# Logics_I2C_SMD_Adapter_v1_4.net
KiCad netlist of a schematic drawn in EAGLE
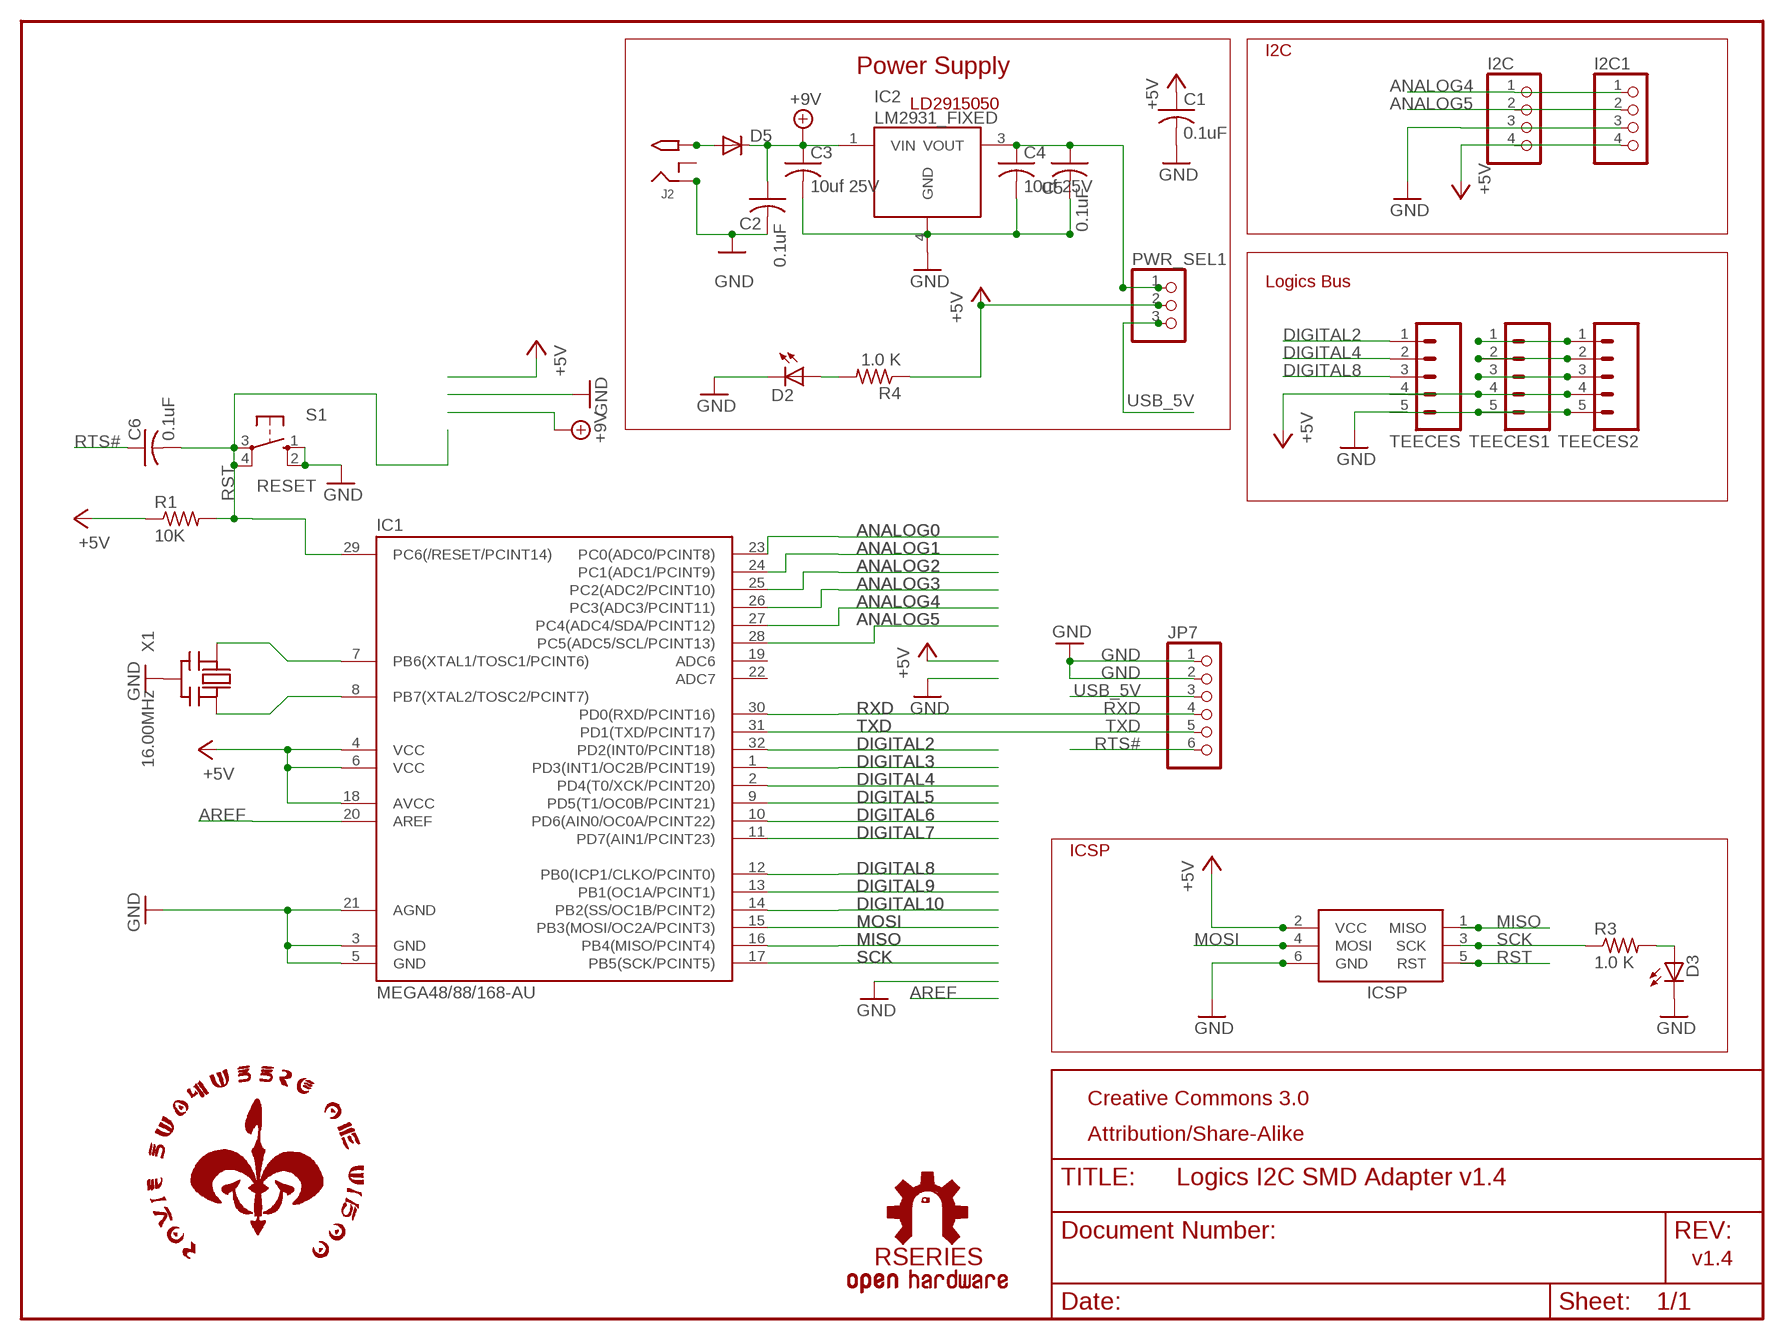
[diagram p0: schematic, sheet 1]

(export (version "E")
  (design (tool "Eeschema 10.0.6"))
  (components
    (comp (ref "C1")
      (value "0.1uF")
      (footprint "eagle-import:C1206K")
      (libsource (lib "eagle-import") (part "C-USC1206K"))
    )
    (comp (ref "C2")
      (value "0.1uF")
      (footprint "eagle-import:C1206K")
      (libsource (lib "eagle-import") (part "C-USC1206K"))
    )
    (comp (ref "C3")
      (value "10uf 25V")
      (footprint "eagle-import:C1206K")
      (libsource (lib "eagle-import") (part "rcl_C-USC1206K"))
    )
    (comp (ref "C4")
      (value "10uf 25V")
      (footprint "eagle-import:C1206K")
      (libsource (lib "eagle-import") (part "rcl_C-USC1206K"))
    )
    (comp (ref "C5")
      (value "0.1uF")
      (footprint "eagle-import:C1206K")
      (libsource (lib "eagle-import") (part "C-USC1206K"))
    )
    (comp (ref "C6")
      (value "0.1uF")
      (footprint "eagle-import:C1206K")
      (libsource (lib "eagle-import") (part "C-USC1206K"))
    )
    (comp (ref "D2")
      (value "LEDCHIPLED_1206")
      (footprint "eagle-import:CHIPLED_1206")
      (libsource (lib "eagle-import") (part "LEDCHIPLED_1206"))
    )
    (comp (ref "D3")
      (value "Green")
      (footprint "eagle-import:CHIPLED_1206")
      (libsource (lib "eagle-import") (part "LEDCHIPLED_1206"))
    )
    (comp (ref "D5")
      (value "DIODE-SMB")
      (footprint "eagle-import:SMB")
      (libsource (lib "eagle-import") (part "DIODE-SMB"))
    )
    (comp (ref "I2C")
      (value "PINHD-1X4CB")
      (footprint "eagle-import:1X04-CB")
      (libsource (lib "eagle-import") (part "PINHD-1X4CB"))
    )
    (comp (ref "I2C1")
      (value "PINHD-1X4CB")
      (footprint "eagle-import:1X04-CB")
      (libsource (lib "eagle-import") (part "PINHD-1X4CB"))
    )
    (comp (ref "IC1")
      (value "MEGA48/88/168-AU")
      (footprint "eagle-import:TQFP32-08")
      (libsource (lib "eagle-import") (part "MEGA48/88/168-AU"))
    )
    (comp (ref "IC2")
      (value "LM2931_FIXED")
      (footprint "eagle-import:DPAK")
      (libsource (lib "eagle-import") (part "LM2931_FIXED"))
    )
    (comp (ref "ICSP")
      (value "AVRISP-6")
      (footprint "eagle-import:AVRISP")
      (libsource (lib "eagle-import") (part "AVRISP-6"))
    )
    (comp (ref "J2")
      (value "2.1MMJACK")
      (footprint "eagle-import:PJ-102A")
      (libsource (lib "eagle-import") (part "2.1MMJACK"))
    )
    (comp (ref "JP7")
      (value "PINHD-1X6CLEAN")
      (footprint "eagle-import:1X06-CLEAN")
      (libsource (lib "eagle-import") (part "PINHD-1X6CLEAN"))
    )
    (comp (ref "PWR_SEL1")
      (value "PINHD-1X3")
      (footprint "eagle-import:1X03")
      (libsource (lib "eagle-import") (part "PINHD-1X3"))
    )
    (comp (ref "R1")
      (value "10K")
      (footprint "eagle-import:R1206")
      (libsource (lib "eagle-import") (part "rcl-ez_R-US_R1206"))
    )
    (comp (ref "R3")
      (value "1.0 K")
      (footprint "eagle-import:M1206")
      (libsource (lib "eagle-import") (part "R-US_M1206"))
    )
    (comp (ref "R4")
      (value "1.0 K")
      (footprint "eagle-import:M1206")
      (libsource (lib "eagle-import") (part "R-US_M1206"))
    )
    (comp (ref "S1")
      (value "RESET")
      (footprint "eagle-import:B3F-10XX")
      (libsource (lib "eagle-import") (part "10-XX"))
    )
    (comp (ref "TEECES")
      (value "M05PTH")
      (footprint "eagle-import:1X05")
      (libsource (lib "eagle-import") (part "M05PTH"))
    )
    (comp (ref "TEECES1")
      (value "M05PTH")
      (footprint "eagle-import:1X05")
      (libsource (lib "eagle-import") (part "M05PTH"))
    )
    (comp (ref "TEECES2")
      (value "M05PTH")
      (footprint "eagle-import:1X05")
      (libsource (lib "eagle-import") (part "M05PTH"))
    )
    (comp (ref "U$1")
      (value "ROYAL-ENGINEERS-OF-NABOOSMALL")
      (footprint "eagle-import:ROYAL-ENGINEERS-OF-NABOO-SMALL")
      (libsource (lib "eagle-import") (part "ROYAL-ENGINEERS-OF-NABOOSMALL"))
    )
    (comp (ref "U$2")
      (value "RSERIES-OSHW-LOGOMEDIUM")
      (footprint "eagle-import:RSERIES-OSHW-LOGO-MEDIUM")
      (libsource (lib "eagle-import") (part "RSERIES-OSHW-LOGOMEDIUM"))
    )
    (comp (ref "X1")
      (value "16.00MHz")
      (footprint "eagle-import:CERM_OSC")
      (libsource (lib "eagle-import") (part "CERMOSCILL"))
    )
  )
  (nets
    (net (code "1") (name "+5V") (class "Default")
      (node (ref "C1") (pin "1") (pinfunction "1_1") (pintype "passive"))
      (node (ref "I2C") (pin "4") (pinfunction "4_4") (pintype "passive"))
      (node (ref "I2C1") (pin "4") (pinfunction "4_4") (pintype "passive"))
      (node (ref "IC1") (pin "18") (pinfunction "AVCC_18") (pintype "passive"))
      (node (ref "IC1") (pin "4") (pinfunction "VCC_4") (pintype "power_in"))
      (node (ref "IC1") (pin "6") (pinfunction "VCC_6") (pintype "power_in"))
      (node (ref "ICSP") (pin "2") (pinfunction "VCC_2") (pintype "power_in"))
      (node (ref "PWR_SEL1") (pin "2") (pinfunction "2_2") (pintype "passive"))
      (node (ref "R1") (pin "1") (pinfunction "1_1") (pintype "passive"))
      (node (ref "R4") (pin "1") (pinfunction "1_1") (pintype "passive"))
      (node (ref "TEECES") (pin "4") (pinfunction "4_4") (pintype "passive"))
      (node (ref "TEECES1") (pin "4") (pinfunction "4_4") (pintype "passive"))
      (node (ref "TEECES2") (pin "4") (pinfunction "4_4") (pintype "passive"))
    )
    (net (code "2") (name "+9V") (class "Default")
      (node (ref "C2") (pin "1") (pinfunction "1_1") (pintype "passive"))
      (node (ref "C3") (pin "1") (pinfunction "1_1") (pintype "passive"))
      (node (ref "D5") (pin "C") (pinfunction "C_C") (pintype "passive"))
      (node (ref "IC2") (pin "1") (pinfunction "VIN_1") (pintype "bidirectional"))
    )
    (net (code "3") (name "/ANALOG0") (class "Default")
      (node (ref "IC1") (pin "23") (pinfunction "PC0(ADC0/PCINT8)_23") (pintype "bidirectional"))
    )
    (net (code "4") (name "/ANALOG1") (class "Default")
      (node (ref "IC1") (pin "24") (pinfunction "PC1(ADC1/PCINT9)_24") (pintype "bidirectional"))
    )
    (net (code "5") (name "/ANALOG2") (class "Default")
      (node (ref "IC1") (pin "25") (pinfunction "PC2(ADC2/PCINT10)_25") (pintype "bidirectional"))
    )
    (net (code "6") (name "/ANALOG3") (class "Default")
      (node (ref "IC1") (pin "26") (pinfunction "PC3(ADC3/PCINT11)_26") (pintype "bidirectional"))
    )
    (net (code "7") (name "/ANALOG4") (class "Default")
      (node (ref "I2C") (pin "1") (pinfunction "1_1") (pintype "passive"))
      (node (ref "I2C1") (pin "1") (pinfunction "1_1") (pintype "passive"))
      (node (ref "IC1") (pin "27") (pinfunction "PC4(ADC4/SDA/PCINT12)_27") (pintype "bidirectional"))
    )
    (net (code "8") (name "/ANALOG5") (class "Default")
      (node (ref "I2C") (pin "2") (pinfunction "2_2") (pintype "passive"))
      (node (ref "I2C1") (pin "2") (pinfunction "2_2") (pintype "passive"))
      (node (ref "IC1") (pin "28") (pinfunction "PC5(ADC5/SCL/PCINT13)_28") (pintype "bidirectional"))
    )
    (net (code "9") (name "/AREF") (class "Default")
      (node (ref "IC1") (pin "20") (pinfunction "AREF_20") (pintype "passive"))
    )
    (net (code "10") (name "/DIGITAL2") (class "Default")
      (node (ref "IC1") (pin "32") (pinfunction "PD2(INT0/PCINT18)_32") (pintype "bidirectional"))
      (node (ref "TEECES") (pin "1") (pinfunction "1_1") (pintype "passive"))
    )
    (net (code "11") (name "/DIGITAL3") (class "Default")
      (node (ref "IC1") (pin "1") (pinfunction "PD3(INT1/OC2B/PCINT19)_1") (pintype "bidirectional"))
    )
    (net (code "12") (name "/DIGITAL4") (class "Default")
      (node (ref "IC1") (pin "2") (pinfunction "PD4(T0/XCK/PCINT20)_2") (pintype "bidirectional"))
      (node (ref "TEECES") (pin "2") (pinfunction "2_2") (pintype "passive"))
    )
    (net (code "13") (name "/DIGITAL5") (class "Default")
      (node (ref "IC1") (pin "9") (pinfunction "PD5(T1/OC0B/PCINT21)_9") (pintype "bidirectional"))
    )
    (net (code "14") (name "/DIGITAL6") (class "Default")
      (node (ref "IC1") (pin "10") (pinfunction "PD6(AIN0/OC0A/PCINT22)_10") (pintype "bidirectional"))
    )
    (net (code "15") (name "/DIGITAL7") (class "Default")
      (node (ref "IC1") (pin "11") (pinfunction "PD7(AIN1/PCINT23)_11") (pintype "bidirectional"))
    )
    (net (code "16") (name "/DIGITAL8") (class "Default")
      (node (ref "IC1") (pin "12") (pinfunction "PB0(ICP1/CLKO/PCINT0)_12") (pintype "bidirectional"))
      (node (ref "TEECES") (pin "3") (pinfunction "3_3") (pintype "passive"))
    )
    (net (code "17") (name "/DIGITAL9") (class "Default")
      (node (ref "IC1") (pin "13") (pinfunction "PB1(OC1A/PCINT1)_13") (pintype "bidirectional"))
    )
    (net (code "18") (name "/DIGITAL10") (class "Default")
      (node (ref "IC1") (pin "14") (pinfunction "PB2(SS/OC1B/PCINT2)_14") (pintype "bidirectional"))
    )
    (net (code "19") (name "/MISO") (class "Default")
      (node (ref "IC1") (pin "16") (pinfunction "PB4(MISO/PCINT4)_16") (pintype "bidirectional"))
      (node (ref "ICSP") (pin "1") (pinfunction "MISO_1") (pintype "input"))
    )
    (net (code "20") (name "/MOSI") (class "Default")
      (node (ref "IC1") (pin "15") (pinfunction "PB3(MOSI/OC2A/PCINT3)_15") (pintype "bidirectional"))
      (node (ref "ICSP") (pin "4") (pinfunction "MOSI_4") (pintype "output"))
    )
    (net (code "21") (name "/RST") (class "Default")
      (node (ref "C6") (pin "2") (pinfunction "2_2") (pintype "passive"))
      (node (ref "IC1") (pin "29") (pinfunction "PC6(/RESET/PCINT14)_29") (pintype "bidirectional"))
      (node (ref "ICSP") (pin "5") (pinfunction "RST_5") (pintype "output"))
      (node (ref "R1") (pin "2") (pinfunction "2_2") (pintype "passive"))
      (node (ref "S1") (pin "3") (pinfunction "P_3") (pintype "passive"))
      (node (ref "S1") (pin "4") (pinfunction "P1_4") (pintype "passive"))
    )
    (net (code "22") (name "/RTS#") (class "Default")
      (node (ref "C6") (pin "1") (pinfunction "1_1") (pintype "passive"))
      (node (ref "JP7") (pin "6") (pinfunction "6_6") (pintype "passive"))
    )
    (net (code "23") (name "/RXD") (class "Default")
      (node (ref "IC1") (pin "30") (pinfunction "PD0(RXD/PCINT16)_30") (pintype "bidirectional"))
      (node (ref "JP7") (pin "4") (pinfunction "4_4") (pintype "passive"))
    )
    (net (code "24") (name "/SCK") (class "Default")
      (node (ref "IC1") (pin "17") (pinfunction "PB5(SCK/PCINT5)_17") (pintype "bidirectional"))
      (node (ref "ICSP") (pin "3") (pinfunction "SCK_3") (pintype "output"))
      (node (ref "R3") (pin "1") (pinfunction "1_1") (pintype "passive"))
    )
    (net (code "25") (name "/TXD") (class "Default")
      (node (ref "IC1") (pin "31") (pinfunction "PD1(TXD/PCINT17)_31") (pintype "bidirectional"))
      (node (ref "JP7") (pin "5") (pinfunction "5_5") (pintype "passive"))
    )
    (net (code "26") (name "/USB_5V") (class "Default")
      (node (ref "JP7") (pin "3") (pinfunction "3_3") (pintype "passive"))
      (node (ref "PWR_SEL1") (pin "3") (pinfunction "3_3") (pintype "passive"))
    )
    (net (code "27") (name "GND") (class "Default")
      (node (ref "C1") (pin "2") (pinfunction "2_2") (pintype "passive"))
      (node (ref "C2") (pin "2") (pinfunction "2_2") (pintype "passive"))
      (node (ref "D2") (pin "C") (pinfunction "C_C") (pintype "passive"))
      (node (ref "D3") (pin "C") (pinfunction "C_C") (pintype "passive"))
      (node (ref "I2C") (pin "3") (pinfunction "3_3") (pintype "passive"))
      (node (ref "I2C1") (pin "3") (pinfunction "3_3") (pintype "passive"))
      (node (ref "IC1") (pin "21") (pinfunction "AGND_21") (pintype "power_in"))
      (node (ref "IC1") (pin "3") (pinfunction "GND_3") (pintype "power_in"))
      (node (ref "IC1") (pin "5") (pinfunction "GND_5") (pintype "power_in"))
      (node (ref "IC2") (pin "4") (pinfunction "GND_4") (pintype "bidirectional"))
      (node (ref "ICSP") (pin "6") (pinfunction "GND_6") (pintype "power_in"))
      (node (ref "J2") (pin "RING") (pinfunction "RING_RING") (pintype "bidirectional"))
      (node (ref "JP7") (pin "1") (pinfunction "1_1") (pintype "passive"))
      (node (ref "JP7") (pin "2") (pinfunction "2_2") (pintype "passive"))
      (node (ref "S1") (pin "1") (pinfunction "S_1") (pintype "passive"))
      (node (ref "S1") (pin "2") (pinfunction "S1_2") (pintype "passive"))
      (node (ref "TEECES") (pin "5") (pinfunction "5_5") (pintype "passive"))
      (node (ref "TEECES1") (pin "5") (pinfunction "5_5") (pintype "passive"))
      (node (ref "TEECES2") (pin "5") (pinfunction "5_5") (pintype "passive"))
      (node (ref "X1") (pin "P$2") (pinfunction "GND_P$2") (pintype "bidirectional"))
    )
    (net (code "28") (name "Net-(C3-Pad2)") (class "Default")
      (node (ref "C3") (pin "2") (pinfunction "2_2") (pintype "passive"))
      (node (ref "C4") (pin "2") (pinfunction "2_2") (pintype "passive"))
      (node (ref "C5") (pin "2") (pinfunction "2_2") (pintype "passive"))
    )
    (net (code "29") (name "Net-(D2-PadA)") (class "Default")
      (node (ref "D2") (pin "A") (pinfunction "A_A") (pintype "passive"))
      (node (ref "R4") (pin "2") (pinfunction "2_2") (pintype "passive"))
    )
    (net (code "30") (name "Net-(D3-PadA)") (class "Default")
      (node (ref "D3") (pin "A") (pinfunction "A_A") (pintype "passive"))
      (node (ref "R3") (pin "2") (pinfunction "2_2") (pintype "passive"))
    )
    (net (code "31") (name "Net-(D5-PadA)") (class "Default")
      (node (ref "D5") (pin "A") (pinfunction "A_A") (pintype "passive"))
      (node (ref "J2") (pin "TIP") (pinfunction "TIP_TIP") (pintype "bidirectional"))
    )
    (net (code "32") (name "Net-(IC1-PB6(XTAL1{slash}TOSC1{slash}PCINT6))") (class "Default")
      (node (ref "IC1") (pin "7") (pinfunction "PB6(XTAL1/TOSC1/PCINT6)_7") (pintype "bidirectional"))
      (node (ref "X1") (pin "P$1") (pinfunction "IN_P$1") (pintype "bidirectional"))
    )
    (net (code "33") (name "Net-(IC1-PB7(XTAL2{slash}TOSC2{slash}PCINT7))") (class "Default")
      (node (ref "IC1") (pin "8") (pinfunction "PB7(XTAL2/TOSC2/PCINT7)_8") (pintype "bidirectional"))
      (node (ref "X1") (pin "P$3") (pinfunction "OUT_P$3") (pintype "bidirectional"))
    )
    (net (code "34") (name "Net-(IC2-VOUT)") (class "Default")
      (node (ref "C4") (pin "1") (pinfunction "1_1") (pintype "passive"))
      (node (ref "C5") (pin "1") (pinfunction "1_1") (pintype "passive"))
      (node (ref "IC2") (pin "3") (pinfunction "VOUT_3") (pintype "bidirectional"))
      (node (ref "PWR_SEL1") (pin "1") (pinfunction "1_1") (pintype "passive"))
    )
    (net (code "35") (name "Net-(TEECES1-Pad1)") (class "Default")
      (node (ref "TEECES1") (pin "1") (pinfunction "1_1") (pintype "passive"))
      (node (ref "TEECES2") (pin "1") (pinfunction "1_1") (pintype "passive"))
    )
    (net (code "36") (name "Net-(TEECES1-Pad2)") (class "Default")
      (node (ref "TEECES1") (pin "2") (pinfunction "2_2") (pintype "passive"))
      (node (ref "TEECES2") (pin "2") (pinfunction "2_2") (pintype "passive"))
    )
    (net (code "37") (name "Net-(TEECES1-Pad3)") (class "Default")
      (node (ref "TEECES1") (pin "3") (pinfunction "3_3") (pintype "passive"))
      (node (ref "TEECES2") (pin "3") (pinfunction "3_3") (pintype "passive"))
    )
    (net (code "38") (name "unconnected-(IC1-ADC6-Pad19)") (class "Default")
      (node (ref "IC1") (pin "19") (pinfunction "ADC6_19") (pintype "passive"))
    )
    (net (code "39") (name "unconnected-(IC1-ADC7-Pad22)") (class "Default")
      (node (ref "IC1") (pin "22") (pinfunction "ADC7_22") (pintype "passive"))
    )
    (net (code "40") (name "unconnected-(J2-PadRING_SW)") (class "Default")
      (node (ref "J2") (pin "RING_SW") (pinfunction "RING_SW_RING_SW") (pintype "bidirectional"))
    )
  )
)
